# Sheet1.net
KiCad netlist of a schematic drawn in Altium Designer
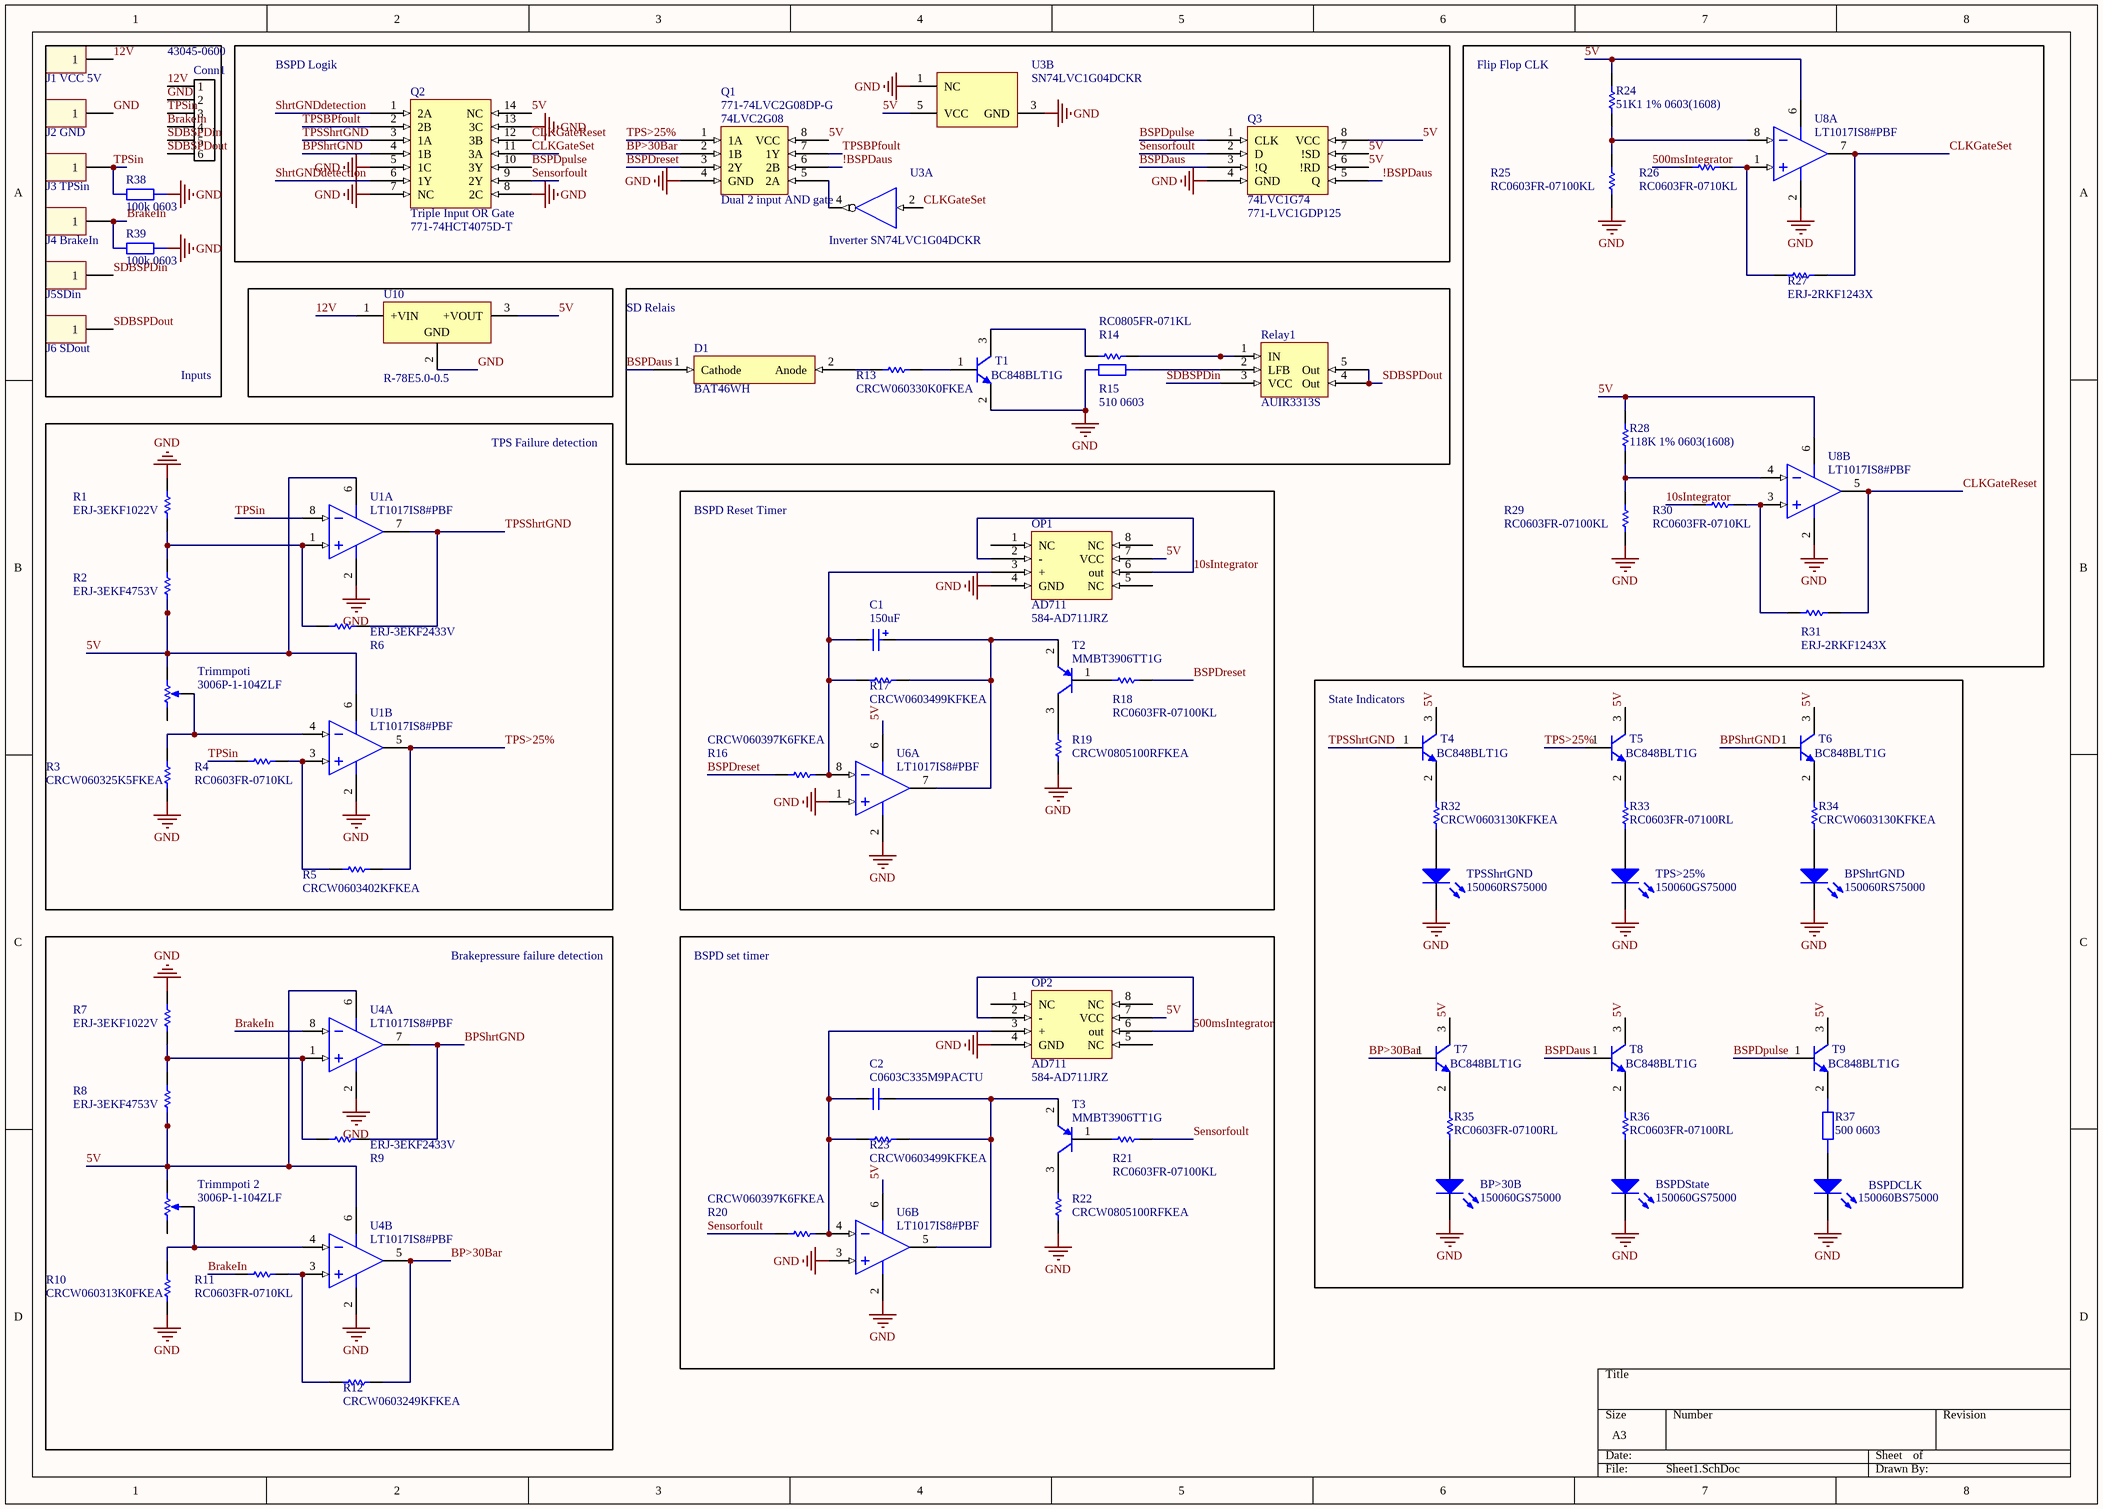
[diagram p0: Sheet1.SchDoc]

(export (version "E")
  (design (tool "Eeschema 10.0.6"))
  (components
    (comp (ref "BP>30B")
      (value "150060GS75000")
      (footprint "0603_A")
      (description "SMD mono-color Chip LED, WL-SMCW, Green")
      (fields (field (name "MANUFACTURER") "Wuerth Elektronik"))
      (libsource (lib "Altium Content Vault") (part "WE-LED_K1A2-2"))
    )
    (comp (ref "BPShrtGND")
      (value "150060RS75000")
      (footprint "0603_A")
      (description "SMD mono-color Chip LED, WL-SMCW, Red")
      (fields (field (name "MANUFACTURER") "Wuerth Elektronik"))
      (libsource (lib "Altium Content Vault") (part "WE-LED_K1A2-2"))
    )
    (comp (ref "BSPDCLK")
      (value "150060BS75000")
      (footprint "0603_A")
      (description "SMD mono-color Chip LED, WL-SMCW, Blue")
      (fields (field (name "MANUFACTURER") "Wuerth Elektronik"))
      (libsource (lib "Altium Content Vault") (part "WE-LED_K1A2-2"))
    )
    (comp (ref "BSPDState")
      (value "150060GS75000")
      (footprint "0603_A")
      (description "SMD mono-color Chip LED, WL-SMCW, Green")
      (fields (field (name "MANUFACTURER") "Wuerth Elektronik"))
      (libsource (lib "Altium Content Vault") (part "WE-LED_K1A2-2"))
    )
    (comp (ref "C1")
      (value "150uF")
      (footprint "WCAP-PSLC_10x12.4")
      (description "WCAP-PSLC Aluminum Polymer Capacitors, size Ф10x12.4mm, 25V DC, 150uF")
      (fields (field (name "PART NUMBER") "875075561006") (field (name "PUBLISHER") "Wurth Elektronik"))
      (libsource (lib "ALTIUM-WCAP-PSLC-rev17b") (part "875075561006"))
    )
    (comp (ref "C2")
      (value "C0603C335M9PACTU")
      (footprint "CAPC1608X90X35NL15T15")
      (fields (field (name "MANUFACTURER") "Kemet"))
      (libsource (lib "Altium Content Vault") (part "CAP"))
    )
    (comp (ref "Conn1")
      (value "43045-0600")
      (footprint "43045-0600")
      (description "Molex Micro-Fit 3.0 6-Pin\r\n600V\r\n8.5A")
      (libsource (lib "Standardbauteile") (part "MicroFit3.0 6-Pin"))
    )
    (comp (ref "D1")
      (value "BAT46WH")
      (footprint "DIOM2715X18N")
      (libsource (lib "Integrated_LibraryLukas") (part "BAT46WH"))
    )
    (comp (ref "J1 VCC 5V")
      (value "61300111121")
      (footprint "61300111121")
      (description "WR-PHD 2.54 mm THT Pin Header, 1p")
      (fields (field (name "PUBLISHER") "Wurth Elektronik"))
      (libsource (lib "ALTIUM-PHD_2_54_THT_DUAL_PIN_HEADER_6130XX21121") (part "61300111121"))
    )
    (comp (ref "J2 GND")
      (value "61300111121")
      (footprint "61300111121")
      (description "WR-PHD 2.54 mm THT Pin Header, 1p")
      (fields (field (name "PUBLISHER") "Wurth Elektronik"))
      (libsource (lib "ALTIUM-PHD_2_54_THT_DUAL_PIN_HEADER_6130XX21121") (part "61300111121"))
    )
    (comp (ref "J3 TPSin")
      (value "61300111121")
      (footprint "61300111121")
      (description "WR-PHD 2.54 mm THT Pin Header, 1p")
      (fields (field (name "PUBLISHER") "Wurth Elektronik"))
      (libsource (lib "ALTIUM-PHD_2_54_THT_DUAL_PIN_HEADER_6130XX21121") (part "61300111121"))
    )
    (comp (ref "J4 BrakeIn")
      (value "61300111121")
      (footprint "61300111121")
      (description "WR-PHD 2.54 mm THT Pin Header, 1p")
      (fields (field (name "PUBLISHER") "Wurth Elektronik"))
      (libsource (lib "ALTIUM-PHD_2_54_THT_DUAL_PIN_HEADER_6130XX21121") (part "61300111121"))
    )
    (comp (ref "J5SDin")
      (value "61300111121")
      (footprint "61300111121")
      (description "WR-PHD 2.54 mm THT Pin Header, 1p")
      (fields (field (name "PUBLISHER") "Wurth Elektronik"))
      (libsource (lib "ALTIUM-PHD_2_54_THT_DUAL_PIN_HEADER_6130XX21121") (part "61300111121"))
    )
    (comp (ref "J6 SDout")
      (value "61300111121")
      (footprint "61300111121")
      (description "WR-PHD 2.54 mm THT Pin Header, 1p")
      (fields (field (name "PUBLISHER") "Wurth Elektronik"))
      (libsource (lib "ALTIUM-PHD_2_54_THT_DUAL_PIN_HEADER_6130XX21121") (part "61300111121"))
    )
    (comp (ref "OP1")
      (value "AD711")
      (footprint "SOIC8; SOIC127P600X175-8N")
      (fields (field (name "SUPPLIER PART NUMBER 1") "584-AD711JRZ"))
      (libsource (lib "Integrated_LibraryLukas") (part "AD711"))
    )
    (comp (ref "OP2")
      (value "AD711")
      (footprint "SOIC8; SOIC127P600X175-8N")
      (fields (field (name "SUPPLIER PART NUMBER 1") "584-AD711JRZ"))
      (libsource (lib "Integrated_LibraryLukas") (part "AD711"))
    )
    (comp (ref "Q1")
      (value "Dual 2 input AND gate")
      (footprint "TSSOP8; TSOP65P400X110-8N")
      (fields (field (name "SUPPLIER PART NUMBER 1") "771-74LVC2G08DP-G"))
      (libsource (lib "Integrated_LibraryLukas") (part "74LVC2G08-Q100"))
    )
    (comp (ref "Q2")
      (value "Triple Input OR Gate")
      (footprint "SOIC14; SOIC127P600X175-14N")
      (fields (field (name "SUPPLIER PART NUMBER 1") "771-74HCT4075D-T"))
      (libsource (lib "Integrated_LibraryLukas") (part "74HCT4075D,653"))
    )
    (comp (ref "Q3")
      (value "74LVC1G74")
      (footprint "TSSOP8; TSOP65P400X110-8N")
      (fields (field (name "SUPPLIER PART NUMBER 1") "771-LVC1GDP125"))
      (libsource (lib "Integrated_LibraryLukas") (part "74LVC1G74"))
    )
    (comp (ref "R1")
      (value "ERJ-3EKF1022V")
      (footprint "RESC1608X55X30LL15T15")
      (fields (field (name "MANUFACTURER") "Panasonic"))
      (libsource (lib "Altium Content Vault") (part "RES"))
    )
    (comp (ref "R2")
      (value "ERJ-3EKF4753V")
      (footprint "RESC1608X55X30LL15T15")
      (fields (field (name "MANUFACTURER") "Panasonic"))
      (libsource (lib "Altium Content Vault") (part "RES"))
    )
    (comp (ref "R3")
      (value "CRCW060325K5FKEA")
      (footprint "RESC1609X50X30ML10T20")
      (fields (field (name "MANUFACTURER") "Vishay Dale"))
      (libsource (lib "Altium Content Vault") (part "RES"))
    )
    (comp (ref "R4")
      (value "RC0603FR-0710KL")
      (footprint "RESC1608X55X25ML10T15")
      (description "Chip Resistor, 10 KOhm, +/- 1%, 01 W, -55 to 155 degC, 0603 (1608 Metric), RoHS, Tape and Reel")
      (fields (field (name "MANUFACTURER") "Yageo") (field (name "TOLERANCE") "1%"))
      (libsource (lib "Altium Content Vault") (part "RES-2"))
    )
    (comp (ref "R5")
      (value "CRCW0603402KFKEA")
      (footprint "RESC1609X50X30ML10T20")
      (fields (field (name "MANUFACTURER") "Vishay Dale"))
      (libsource (lib "Altium Content Vault") (part "RES"))
    )
    (comp (ref "R6")
      (value "ERJ-3EKF2433V")
      (footprint "RESC1608X55X30ML15T15")
      (fields (field (name "MANUFACTURER") "Panasonic"))
      (libsource (lib "Altium Content Vault") (part "RES"))
    )
    (comp (ref "R7")
      (value "ERJ-3EKF1022V")
      (footprint "RESC1608X55X30LL15T15")
      (fields (field (name "MANUFACTURER") "Panasonic"))
      (libsource (lib "Altium Content Vault") (part "RES"))
    )
    (comp (ref "R8")
      (value "ERJ-3EKF4753V")
      (footprint "RESC1608X55X30LL15T15")
      (fields (field (name "MANUFACTURER") "Panasonic"))
      (libsource (lib "Altium Content Vault") (part "RES"))
    )
    (comp (ref "R9")
      (value "ERJ-3EKF2433V")
      (footprint "RESC1608X55X30ML15T15")
      (fields (field (name "MANUFACTURER") "Panasonic"))
      (libsource (lib "Altium Content Vault") (part "RES"))
    )
    (comp (ref "R10")
      (value "CRCW060313K0FKEA")
      (footprint "RESC1609X50X30NL10T20")
      (fields (field (name "MANUFACTURER") "Vishay Dale"))
      (libsource (lib "Altium Content Vault") (part "RES"))
    )
    (comp (ref "R11")
      (value "RC0603FR-0710KL")
      (footprint "RESC1608X55X25ML10T15")
      (description "Chip Resistor, 10 KOhm, +/- 1%, 01 W, -55 to 155 degC, 0603 (1608 Metric), RoHS, Tape and Reel")
      (fields (field (name "MANUFACTURER") "Yageo") (field (name "TOLERANCE") "1%"))
      (libsource (lib "Altium Content Vault") (part "RES-2"))
    )
    (comp (ref "R12")
      (value "CRCW0603249KFKEA")
      (footprint "RESC1609X50X30NL10T20")
      (fields (field (name "MANUFACTURER") "Vishay Dale"))
      (libsource (lib "Altium Content Vault") (part "RES"))
    )
    (comp (ref "R13")
      (value "CRCW060330K0FKEA")
      (footprint "RESC1609X50X30LL10T20")
      (fields (field (name "MANUFACTURER") "Vishay Dale"))
      (libsource (lib "Altium Content Vault") (part "RES"))
    )
    (comp (ref "R14")
      (value "RC0805FR-071KL")
      (footprint "RESC2013X60X35ML10T20")
      (description "Chip Resistor, 1 KOhm, +/- 1%, 125 mW, -55 to 155 degC, 0805 (2012 Metric), RoHS, Tape and Reel")
      (fields (field (name "TOLERANCE") "1%") (field (name "MANUFACTURER") "Yageo"))
      (libsource (lib "Altium Content Vault") (part "RES-2"))
    )
    (comp (ref "R15")
      (value "510 0603")
      (footprint "STACKPOLE CSR0603")
      (description "Resistor with multiple footprints")
      (fields (field (name "Comment") "SMD Resistor"))
      (libsource (lib "Standardbauteile") (part "SMD Resistor"))
    )
    (comp (ref "R16")
      (value "CRCW060397K6FKEA")
      (footprint "RESC1609X50X30LL10T20")
      (fields (field (name "MANUFACTURER") "Vishay Dale"))
      (libsource (lib "Altium Content Vault") (part "RES"))
    )
    (comp (ref "R17")
      (value "CRCW0603499KFKEA")
      (footprint "RESC1609X50X30NL10T20")
      (fields (field (name "MANUFACTURER") "Vishay Dale"))
      (libsource (lib "Altium Content Vault") (part "RES"))
    )
    (comp (ref "R18")
      (value "RC0603FR-07100KL")
      (footprint "RESC1608X55X25ML10T15")
      (description "Chip Resistor, 100 KOhm, +/- 1%, 0.1 W, -55 to 155 degC, 0603 (1608 Metric), RoHS, Tape and Reel")
      (fields (field (name "MANUFACTURER") "Yageo") (field (name "TOLERANCE") "1%"))
      (libsource (lib "Altium Content Vault") (part "RES-2"))
    )
    (comp (ref "R19")
      (value "CRCW0805100RFKEA")
      (footprint "RESC2013X50X30LL20T20")
      (fields (field (name "MANUFACTURER") "Vishay Dale"))
      (libsource (lib "Altium Content Vault") (part "RES"))
    )
    (comp (ref "R20")
      (value "CRCW060397K6FKEA")
      (footprint "RESC1609X50X30LL10T20")
      (fields (field (name "MANUFACTURER") "Vishay Dale"))
      (libsource (lib "Altium Content Vault") (part "RES"))
    )
    (comp (ref "R21")
      (value "RC0603FR-07100KL")
      (footprint "RESC1608X55X25ML10T15")
      (description "Chip Resistor, 100 KOhm, +/- 1%, 0.1 W, -55 to 155 degC, 0603 (1608 Metric), RoHS, Tape and Reel")
      (fields (field (name "MANUFACTURER") "Yageo") (field (name "TOLERANCE") "1%"))
      (libsource (lib "Altium Content Vault") (part "RES-2"))
    )
    (comp (ref "R22")
      (value "CRCW0805100RFKEA")
      (footprint "RESC2013X50X30LL20T20")
      (fields (field (name "MANUFACTURER") "Vishay Dale"))
      (libsource (lib "Altium Content Vault") (part "RES"))
    )
    (comp (ref "R23")
      (value "CRCW0603499KFKEA")
      (footprint "RESC1609X50X30NL10T20")
      (fields (field (name "MANUFACTURER") "Vishay Dale"))
      (libsource (lib "Altium Content Vault") (part "RES"))
    )
    (comp (ref "R24")
      (value "51K1 1% 0603(1608)")
      (footprint "RESC0603(1608)_L")
      (description "51K1 0.1W 1% 0603 (1608 Metric)  SMD")
      (fields (field (name "TOLERANCE") "1 %") (field (name "POWER") "0.1 W"))
      (libsource (lib "Altium Content Vault") (part "RES"))
    )
    (comp (ref "R25")
      (value "RC0603FR-07100KL")
      (footprint "RESC1608X55X25ML10T15")
      (description "Chip Resistor, 100 KOhm, +/- 1%, 0.1 W, -55 to 155 degC, 0603 (1608 Metric), RoHS, Tape and Reel")
      (fields (field (name "MANUFACTURER") "Yageo") (field (name "TOLERANCE") "1%"))
      (libsource (lib "Altium Content Vault") (part "RES-2"))
    )
    (comp (ref "R26")
      (value "RC0603FR-0710KL")
      (footprint "RESC1608X55X25ML10T15")
      (description "Chip Resistor, 10 KOhm, +/- 1%, 01 W, -55 to 155 degC, 0603 (1608 Metric), RoHS, Tape and Reel")
      (fields (field (name "MANUFACTURER") "Yageo") (field (name "TOLERANCE") "1%"))
      (libsource (lib "Altium Content Vault") (part "RES-2"))
    )
    (comp (ref "R27")
      (value "ERJ-2RKF1243X")
      (footprint "RESC1005X40X25NL05T05")
      (fields (field (name "MANUFACTURER") "Panasonic"))
      (libsource (lib "Altium Content Vault") (part "RES"))
    )
    (comp (ref "R28")
      (value "118K 1% 0603(1608)")
      (footprint "RESC0603(1608)_M")
      (description "118K 0.1W 1% 0603 (1608 Metric)  SMD")
      (fields (field (name "POWER") "0.1 W") (field (name "TOLERANCE") "1 %"))
      (libsource (lib "Altium Content Vault") (part "RES"))
    )
    (comp (ref "R29")
      (value "RC0603FR-07100KL")
      (footprint "RESC1608X55X25ML10T15")
      (description "Chip Resistor, 100 KOhm, +/- 1%, 0.1 W, -55 to 155 degC, 0603 (1608 Metric), RoHS, Tape and Reel")
      (fields (field (name "MANUFACTURER") "Yageo") (field (name "TOLERANCE") "1%"))
      (libsource (lib "Altium Content Vault") (part "RES-2"))
    )
    (comp (ref "R30")
      (value "RC0603FR-0710KL")
      (footprint "RESC1608X55X25ML10T15")
      (description "Chip Resistor, 10 KOhm, +/- 1%, 01 W, -55 to 155 degC, 0603 (1608 Metric), RoHS, Tape and Reel")
      (fields (field (name "MANUFACTURER") "Yageo") (field (name "TOLERANCE") "1%"))
      (libsource (lib "Altium Content Vault") (part "RES-2"))
    )
    (comp (ref "R31")
      (value "ERJ-2RKF1243X")
      (footprint "RESC1005X40X25NL05T05")
      (fields (field (name "MANUFACTURER") "Panasonic"))
      (libsource (lib "Altium Content Vault") (part "RES"))
    )
    (comp (ref "R32")
      (value "CRCW0603130KFKEA")
      (footprint "RESC1609X50X30NL10T20")
      (fields (field (name "MANUFACTURER") "Vishay Dale"))
      (libsource (lib "Altium Content Vault") (part "RES"))
    )
    (comp (ref "R33")
      (value "RC0603FR-07100RL")
      (footprint "RESC1608X55X25ML10T15")
      (description "Chip Resistor, 100 Ohm, +/- 1%, 0.1 W, -55 to 155 degC, 0603 (1608 Metric), RoHS, Tape and Reel")
      (fields (field (name "TOLERANCE") "1%") (field (name "MANUFACTURER") "Yageo"))
      (libsource (lib "Altium Content Vault") (part "RES-2"))
    )
    (comp (ref "R34")
      (value "CRCW0603130KFKEA")
      (footprint "RESC1609X50X30NL10T20")
      (fields (field (name "MANUFACTURER") "Vishay Dale"))
      (libsource (lib "Altium Content Vault") (part "RES"))
    )
    (comp (ref "R35")
      (value "RC0603FR-07100RL")
      (footprint "RESC1608X55X25ML10T15")
      (description "Chip Resistor, 100 Ohm, +/- 1%, 0.1 W, -55 to 155 degC, 0603 (1608 Metric), RoHS, Tape and Reel")
      (fields (field (name "TOLERANCE") "1%") (field (name "MANUFACTURER") "Yageo"))
      (libsource (lib "Altium Content Vault") (part "RES-2"))
    )
    (comp (ref "R36")
      (value "RC0603FR-07100RL")
      (footprint "RESC1608X55X25ML10T15")
      (description "Chip Resistor, 100 Ohm, +/- 1%, 0.1 W, -55 to 155 degC, 0603 (1608 Metric), RoHS, Tape and Reel")
      (fields (field (name "TOLERANCE") "1%") (field (name "MANUFACTURER") "Yageo"))
      (libsource (lib "Altium Content Vault") (part "RES-2"))
    )
    (comp (ref "R37")
      (value "500 0603")
      (footprint "STACKPOLE CSR0603")
      (description "Resistor with multiple footprints")
      (fields (field (name "Comment") "SMD Resistor"))
      (libsource (lib "Standardbauteile") (part "SMD Resistor"))
    )
    (comp (ref "R38")
      (value "100k 0603")
      (footprint "STACKPOLE CSR0603")
      (description "Resistor with multiple footprints")
      (fields (field (name "Comment") "SMD Resistor"))
      (libsource (lib "Standardbauteile") (part "SMD Resistor"))
    )
    (comp (ref "R39")
      (value "100k 0603")
      (footprint "STACKPOLE CSR0603")
      (description "Resistor with multiple footprints")
      (fields (field (name "Comment") "SMD Resistor"))
      (libsource (lib "Standardbauteile") (part "SMD Resistor"))
    )
    (comp (ref "Relay1")
      (value "AUIR3313S")
      (footprint "D2PAK5 ;DPAK228P1524X483-5N")
      (libsource (lib "Integrated_LibraryLukas") (part "AUIR3313S"))
    )
    (comp (ref "T1")
      (value "BC848BLT1G")
      (footprint "ONSC-SOT-23-3-318-08_V")
      (description "General Purpose Transistor, NPN Silicon, 3-Pin SOT-23, Pb-Free, Tape and Reel")
      (fields (field (name "MANUFACTURER") "On Semiconductor"))
      (libsource (lib "Altium Content Vault") (part "ONSC-NPN-B1E2C3-3"))
    )
    (comp (ref "T2")
      (value "MMBT3906TT1G")
      (footprint "ONSC-SC-75-3-463-01_V")
      (description "General Purpose Transistor, PNP Silicon, 3-Pin SC-75, Pb-Free, Tape and Reel")
      (fields (field (name "MANUFACTURER") "On Semiconductor"))
      (libsource (lib "Altium Content Vault") (part "ONSC-PNP-B1E2C3-3"))
    )
    (comp (ref "T3")
      (value "MMBT3906TT1G")
      (footprint "ONSC-SC-75-3-463-01_V")
      (description "General Purpose Transistor, PNP Silicon, 3-Pin SC-75, Pb-Free, Tape and Reel")
      (fields (field (name "MANUFACTURER") "On Semiconductor"))
      (libsource (lib "Altium Content Vault") (part "ONSC-PNP-B1E2C3-3"))
    )
    (comp (ref "T4")
      (value "BC848BLT1G")
      (footprint "ONSC-SOT-23-3-318-08_V")
      (description "General Purpose Transistor, NPN Silicon, 3-Pin SOT-23, Pb-Free, Tape and Reel")
      (fields (field (name "MANUFACTURER") "On Semiconductor"))
      (libsource (lib "Altium Content Vault") (part "ONSC-NPN-B1E2C3-3"))
    )
    (comp (ref "T5")
      (value "BC848BLT1G")
      (footprint "ONSC-SOT-23-3-318-08_V")
      (description "General Purpose Transistor, NPN Silicon, 3-Pin SOT-23, Pb-Free, Tape and Reel")
      (fields (field (name "MANUFACTURER") "On Semiconductor"))
      (libsource (lib "Altium Content Vault") (part "ONSC-NPN-B1E2C3-3"))
    )
    (comp (ref "T6")
      (value "BC848BLT1G")
      (footprint "ONSC-SOT-23-3-318-08_V")
      (description "General Purpose Transistor, NPN Silicon, 3-Pin SOT-23, Pb-Free, Tape and Reel")
      (fields (field (name "MANUFACTURER") "On Semiconductor"))
      (libsource (lib "Altium Content Vault") (part "ONSC-NPN-B1E2C3-3"))
    )
    (comp (ref "T7")
      (value "BC848BLT1G")
      (footprint "ONSC-SOT-23-3-318-08_V")
      (description "General Purpose Transistor, NPN Silicon, 3-Pin SOT-23, Pb-Free, Tape and Reel")
      (fields (field (name "MANUFACTURER") "On Semiconductor"))
      (libsource (lib "Altium Content Vault") (part "ONSC-NPN-B1E2C3-3"))
    )
    (comp (ref "T8")
      (value "BC848BLT1G")
      (footprint "ONSC-SOT-23-3-318-08_V")
      (description "General Purpose Transistor, NPN Silicon, 3-Pin SOT-23, Pb-Free, Tape and Reel")
      (fields (field (name "MANUFACTURER") "On Semiconductor"))
      (libsource (lib "Altium Content Vault") (part "ONSC-NPN-B1E2C3-3"))
    )
    (comp (ref "T9")
      (value "BC848BLT1G")
      (footprint "ONSC-SOT-23-3-318-08_V")
      (description "General Purpose Transistor, NPN Silicon, 3-Pin SOT-23, Pb-Free, Tape and Reel")
      (fields (field (name "MANUFACTURER") "On Semiconductor"))
      (libsource (lib "Altium Content Vault") (part "ONSC-NPN-B1E2C3-3"))
    )
    (comp (ref "TPS>25%")
      (value "150060GS75000")
      (footprint "0603_A")
      (description "SMD mono-color Chip LED, WL-SMCW, Green")
      (fields (field (name "MANUFACTURER") "Wuerth Elektronik"))
      (libsource (lib "Altium Content Vault") (part "WE-LED_K1A2-2"))
    )
    (comp (ref "TPSShrtGND")
      (value "150060RS75000")
      (footprint "0603_A")
      (description "SMD mono-color Chip LED, WL-SMCW, Red")
      (fields (field (name "MANUFACTURER") "Wuerth Elektronik"))
      (libsource (lib "Altium Content Vault") (part "WE-LED_K1A2-2"))
    )
    (comp (ref "Trimmpoti")
      (value "3006P-1-104ZLF")
      (footprint "BOUR-3006P-3_V")
      (description "Trimming Potentiometer, 100K Ohm +/- 10%, -55 to 125 degC, 3-Pin 19.05 x 4.83 x 6.6 mm THD, RoHS")
      (fields (field (name "MANUFACTURER") "Bourns"))
      (libsource (lib "Altium Content Vault") (part "BOUR-3006P-3"))
    )
    (comp (ref "Trimmpoti 2")
      (value "3006P-1-104ZLF")
      (footprint "BOUR-3006P-3_V")
      (description "Trimming Potentiometer, 100K Ohm +/- 10%, -55 to 125 degC, 3-Pin 19.05 x 4.83 x 6.6 mm THD, RoHS")
      (fields (field (name "MANUFACTURER") "Bourns"))
      (libsource (lib "Altium Content Vault") (part "BOUR-3006P-3"))
    )
    (comp (ref "U1")
      (value "LT1017IS8#PBF")
      (footprint "LT-S8_N")
      (description "Micropower Comparator, 2 Channels, 1.2 to 40 V, -40 to +85 degC, 8-pin SOP (S8)")
      (fields (field (name "MANUFACTURER") "Linear Technology") (field (name "GENERIC PART NUMBER") "LT1017"))
      (libsource (lib "Altium Content Vault") (part "LT-LT1017-SO8"))
    )
    (comp (ref "U3")
      (value "Inverter SN74LVC1G04DCKR")
      (footprint "DCK0005A_N")
      (description "Single Inverter, DCK0005A, LARGE T&R")
      (fields
        (field (name "GENERIC PART NUMBER") "SN74LVC1G04")
        (field (name "MANUFACTURER") "Texas Instruments")
      )
      (libsource (lib "Altium Content Vault") (part "TI-SN74XXX1XX4-XX-5"))
    )
    (comp (ref "U4")
      (value "LT1017IS8#PBF")
      (footprint "LT-S8_N")
      (description "Micropower Comparator, 2 Channels, 1.2 to 40 V, -40 to +85 degC, 8-pin SOP (S8)")
      (fields (field (name "MANUFACTURER") "Linear Technology") (field (name "GENERIC PART NUMBER") "LT1017"))
      (libsource (lib "Altium Content Vault") (part "LT-LT1017-SO8"))
    )
    (comp (ref "U6")
      (value "LT1017IS8#PBF")
      (footprint "LT-S8_N")
      (description "Micropower Comparator, 2 Channels, 1.2 to 40 V, -40 to +85 degC, 8-pin SOP (S8)")
      (fields (field (name "MANUFACTURER") "Linear Technology") (field (name "GENERIC PART NUMBER") "LT1017"))
      (libsource (lib "Altium Content Vault") (part "LT-LT1017-SO8"))
    )
    (comp (ref "U8")
      (value "LT1017IS8#PBF")
      (footprint "LT-S8_N")
      (description "Micropower Comparator, 2 Channels, 1.2 to 40 V, -40 to +85 degC, 8-pin SOP (S8)")
      (fields (field (name "MANUFACTURER") "Linear Technology") (field (name "GENERIC PART NUMBER") "LT1017"))
      (libsource (lib "Altium Content Vault") (part "LT-LT1017-SO8"))
    )
    (comp (ref "U10")
      (value "R-78E5.0-0.5")
      (footprint "REPO-R-78E-0.5-3_V")
      (description "DC/DC-Converter, 5 V Single Output, 500 mA, -40 to 85 degC, 3-Pin THD, RoHS, Tube")
      (fields (field (name "MANUFACTURER") "Recom Power"))
      (libsource (lib "Altium Content Vault") (part "REPO-R-78XX-3"))
    )
  )
  (nets
    (net (code "1") (name "/!BSPDaus") (class "Default")
      (node (ref "Q1") (pin "6") (pinfunction "2B_6") (pintype "input"))
      (node (ref "Q3") (pin "5") (pinfunction "Q_5") (pintype "input"))
    )
    (net (code "2") (name "/5V") (class "Default")
      (node (ref "OP1") (pin "7") (pinfunction "VCC_7") (pintype "input"))
      (node (ref "OP2") (pin "7") (pinfunction "VCC_7") (pintype "input"))
      (node (ref "Q1") (pin "8") (pinfunction "VCC_8") (pintype "input"))
      (node (ref "Q2") (pin "14") (pinfunction "NC_14") (pintype "input"))
      (node (ref "Q3") (pin "6") (pinfunction "!RD_6") (pintype "input"))
      (node (ref "Q3") (pin "7") (pinfunction "!SD_7") (pintype "input"))
      (node (ref "Q3") (pin "8") (pinfunction "VCC_8") (pintype "input"))
      (node (ref "R2") (pin "1") (pinfunction "1_1") (pintype "passive"))
      (node (ref "R24") (pin "2") (pinfunction "2_2") (pintype "passive"))
      (node (ref "R28") (pin "2") (pinfunction "2_2") (pintype "passive"))
      (node (ref "R8") (pin "1") (pinfunction "1_1") (pintype "passive"))
      (node (ref "T4") (pin "3") (pinfunction "C_3") (pintype "passive"))
      (node (ref "T5") (pin "3") (pinfunction "C_3") (pintype "passive"))
      (node (ref "T6") (pin "3") (pinfunction "C_3") (pintype "passive"))
      (node (ref "T7") (pin "3") (pinfunction "C_3") (pintype "passive"))
      (node (ref "T8") (pin "3") (pinfunction "C_3") (pintype "passive"))
      (node (ref "T9") (pin "3") (pinfunction "C_3") (pintype "passive"))
      (node (ref "Trimmpoti") (pin "1") (pinfunction "CCW_1") (pintype "passive"))
      (node (ref "Trimmpoti 2") (pin "1") (pinfunction "CCW_1") (pintype "passive"))
      (node (ref "U1") (pin "6") (pinfunction "V+_6") (pintype "power_in"))
      (node (ref "U10") (pin "3") (pinfunction "+VOUT_3") (pintype "power_in"))
      (node (ref "U3") (pin "5") (pinfunction "VCC_5") (pintype "power_in"))
      (node (ref "U4") (pin "6") (pinfunction "V+_6") (pintype "power_in"))
      (node (ref "U6") (pin "6") (pinfunction "V+_6") (pintype "power_in"))
      (node (ref "U8") (pin "6") (pinfunction "V+_6") (pintype "power_in"))
    )
    (net (code "3") (name "/10sIntegrator") (class "Default")
      (node (ref "OP1") (pin "2") (pinfunction "-_2") (pintype "input"))
      (node (ref "OP1") (pin "6") (pinfunction "out_6") (pintype "input"))
      (node (ref "R30") (pin "1") (pinfunction "1_1") (pintype "passive"))
    )
    (net (code "4") (name "/12V") (class "Default")
      (node (ref "Conn1") (pin "1") (pinfunction "1_1") (pintype "passive"))
      (node (ref "J1 VCC 5V") (pin "1") (pinfunction "1_1") (pintype "passive"))
      (node (ref "U10") (pin "1") (pinfunction "+VIN_1") (pintype "power_in"))
    )
    (net (code "5") (name "/500msIntegrator") (class "Default")
      (node (ref "OP2") (pin "2") (pinfunction "-_2") (pintype "input"))
      (node (ref "OP2") (pin "6") (pinfunction "out_6") (pintype "input"))
      (node (ref "R26") (pin "1") (pinfunction "1_1") (pintype "passive"))
    )
    (net (code "6") (name "/BP>30Bar") (class "Default")
      (node (ref "Q1") (pin "2") (pinfunction "1B_2") (pintype "input"))
      (node (ref "R12") (pin "2") (pinfunction "2_2") (pintype "passive"))
      (node (ref "T7") (pin "1") (pinfunction "B_1") (pintype "passive"))
      (node (ref "U4") (pin "5") (pinfunction "OUT_B_5") (pintype "open_collector"))
    )
    (net (code "7") (name "/BPShrtGND") (class "Default")
      (node (ref "Q2") (pin "4") (pinfunction "1B_4") (pintype "input"))
      (node (ref "R9") (pin "2") (pinfunction "2_2") (pintype "passive"))
      (node (ref "T6") (pin "1") (pinfunction "B_1") (pintype "passive"))
      (node (ref "U4") (pin "7") (pinfunction "OUT_A_7") (pintype "open_collector"))
    )
    (net (code "8") (name "/BSPDaus") (class "Default")
      (node (ref "D1") (pin "1") (pinfunction "Cathode_1") (pintype "input"))
      (node (ref "Q3") (pin "3") (pinfunction "!Q_3") (pintype "input"))
      (node (ref "T8") (pin "1") (pinfunction "B_1") (pintype "passive"))
    )
    (net (code "9") (name "/BSPDpulse") (class "Default")
      (node (ref "Q2") (pin "10") (pinfunction "3Y_10") (pintype "input"))
      (node (ref "Q3") (pin "1") (pinfunction "CLK_1") (pintype "input"))
      (node (ref "T9") (pin "1") (pinfunction "B_1") (pintype "passive"))
    )
    (net (code "10") (name "/BSPDreset") (class "Default")
      (node (ref "Q1") (pin "3") (pinfunction "2Y_3") (pintype "input"))
      (node (ref "R16") (pin "1") (pinfunction "1_1") (pintype "passive"))
      (node (ref "R18") (pin "1") (pinfunction "1_1") (pintype "passive"))
    )
    (net (code "11") (name "/BrakeIn") (class "Default")
      (node (ref "Conn1") (pin "4") (pinfunction "4_4") (pintype "passive"))
      (node (ref "J4 BrakeIn") (pin "1") (pinfunction "1_1") (pintype "passive"))
      (node (ref "R11") (pin "1") (pinfunction "1_1") (pintype "passive"))
      (node (ref "R39") (pin "1") (pinfunction "1_1") (pintype "passive"))
      (node (ref "U4") (pin "8") (pinfunction "-IN_A_8") (pintype "input"))
    )
    (net (code "12") (name "/CLKGateReset") (class "Default")
      (node (ref "Q2") (pin "12") (pinfunction "3B_12") (pintype "input"))
      (node (ref "R31") (pin "2") (pinfunction "2_2") (pintype "passive"))
      (node (ref "U8") (pin "5") (pinfunction "OUT_B_5") (pintype "open_collector"))
    )
    (net (code "13") (name "/CLKGateSet") (class "Default")
      (node (ref "Q2") (pin "11") (pinfunction "3A_11") (pintype "input"))
      (node (ref "R27") (pin "2") (pinfunction "2_2") (pintype "passive"))
      (node (ref "U3") (pin "2") (pinfunction "A_2") (pintype "input"))
      (node (ref "U8") (pin "7") (pinfunction "OUT_A_7") (pintype "open_collector"))
    )
    (net (code "14") (name "/SDBSPDin") (class "Default")
      (node (ref "Conn1") (pin "5") (pinfunction "5_5") (pintype "passive"))
      (node (ref "J5SDin") (pin "1") (pinfunction "1_1") (pintype "passive"))
      (node (ref "Relay1") (pin "3") (pinfunction "VCC_3") (pintype "input"))
    )
    (net (code "15") (name "/SDBSPDout") (class "Default")
      (node (ref "Conn1") (pin "6") (pinfunction "6_6") (pintype "passive"))
      (node (ref "J6 SDout") (pin "1") (pinfunction "1_1") (pintype "passive"))
      (node (ref "Relay1") (pin "4") (pinfunction "Out_4") (pintype "input"))
      (node (ref "Relay1") (pin "5") (pinfunction "Out_5") (pintype "input"))
    )
    (net (code "16") (name "/Sensorfoult") (class "Default")
      (node (ref "Q2") (pin "9") (pinfunction "2Y_9") (pintype "input"))
      (node (ref "Q3") (pin "2") (pinfunction "D_2") (pintype "input"))
      (node (ref "R20") (pin "1") (pinfunction "1_1") (pintype "passive"))
      (node (ref "R21") (pin "1") (pinfunction "1_1") (pintype "passive"))
    )
    (net (code "17") (name "/ShrtGNDdetection") (class "Default")
      (node (ref "Q2") (pin "1") (pinfunction "2A_1") (pintype "input"))
      (node (ref "Q2") (pin "6") (pinfunction "1Y_6") (pintype "input"))
    )
    (net (code "18") (name "/TPS>25%") (class "Default")
      (node (ref "Q1") (pin "1") (pinfunction "1A_1") (pintype "input"))
      (node (ref "R5") (pin "2") (pinfunction "2_2") (pintype "passive"))
      (node (ref "T5") (pin "1") (pinfunction "B_1") (pintype "passive"))
      (node (ref "U1") (pin "5") (pinfunction "OUT_B_5") (pintype "open_collector"))
    )
    (net (code "19") (name "/TPSBPfoult") (class "Default")
      (node (ref "Q1") (pin "7") (pinfunction "1Y_7") (pintype "input"))
      (node (ref "Q2") (pin "2") (pinfunction "2B_2") (pintype "input"))
    )
    (net (code "20") (name "/TPSShrtGND") (class "Default")
      (node (ref "Q2") (pin "3") (pinfunction "1A_3") (pintype "input"))
      (node (ref "R6") (pin "2") (pinfunction "2_2") (pintype "passive"))
      (node (ref "T4") (pin "1") (pinfunction "B_1") (pintype "passive"))
      (node (ref "U1") (pin "7") (pinfunction "OUT_A_7") (pintype "open_collector"))
    )
    (net (code "21") (name "/TPSin") (class "Default")
      (node (ref "Conn1") (pin "3") (pinfunction "3_3") (pintype "passive"))
      (node (ref "J3 TPSin") (pin "1") (pinfunction "1_1") (pintype "passive"))
      (node (ref "R38") (pin "1") (pinfunction "1_1") (pintype "passive"))
      (node (ref "R4") (pin "1") (pinfunction "1_1") (pintype "passive"))
      (node (ref "U1") (pin "8") (pinfunction "-IN_A_8") (pintype "input"))
    )
    (net (code "22") (name "GND") (class "Default")
      (node (ref "BP>30B") (pin "1") (pinfunction "K_1") (pintype "passive"))
      (node (ref "BPShrtGND") (pin "1") (pinfunction "K_1") (pintype "passive"))
      (node (ref "BSPDCLK") (pin "1") (pinfunction "K_1") (pintype "passive"))
      (node (ref "BSPDState") (pin "1") (pinfunction "K_1") (pintype "passive"))
      (node (ref "Conn1") (pin "2") (pinfunction "2_2") (pintype "passive"))
      (node (ref "J2 GND") (pin "1") (pinfunction "1_1") (pintype "passive"))
      (node (ref "OP1") (pin "4") (pinfunction "GND_4") (pintype "input"))
      (node (ref "OP2") (pin "4") (pinfunction "GND_4") (pintype "input"))
      (node (ref "Q1") (pin "4") (pinfunction "GND_4") (pintype "input"))
      (node (ref "Q2") (pin "13") (pinfunction "3C_13") (pintype "input"))
      (node (ref "Q2") (pin "5") (pinfunction "1C_5") (pintype "input"))
      (node (ref "Q2") (pin "7") (pinfunction "NC_7") (pintype "input"))
      (node (ref "Q2") (pin "8") (pinfunction "2C_8") (pintype "input"))
      (node (ref "Q3") (pin "4") (pinfunction "GND_4") (pintype "input"))
      (node (ref "R1") (pin "2") (pinfunction "2_2") (pintype "passive"))
      (node (ref "R10") (pin "1") (pinfunction "1_1") (pintype "passive"))
      (node (ref "R15") (pin "1") (pinfunction "1_1") (pintype "passive"))
      (node (ref "R19") (pin "2") (pinfunction "2_2") (pintype "passive"))
      (node (ref "R22") (pin "2") (pinfunction "2_2") (pintype "passive"))
      (node (ref "R25") (pin "1") (pinfunction "1_1") (pintype "passive"))
      (node (ref "R29") (pin "1") (pinfunction "1_1") (pintype "passive"))
      (node (ref "R3") (pin "1") (pinfunction "1_1") (pintype "passive"))
      (node (ref "R38") (pin "2") (pinfunction "2_2") (pintype "passive"))
      (node (ref "R39") (pin "2") (pinfunction "2_2") (pintype "passive"))
      (node (ref "R7") (pin "2") (pinfunction "2_2") (pintype "passive"))
      (node (ref "T1") (pin "2") (pinfunction "E_2") (pintype "passive"))
      (node (ref "TPS>25%") (pin "1") (pinfunction "K_1") (pintype "passive"))
      (node (ref "TPSShrtGND") (pin "1") (pinfunction "K_1") (pintype "passive"))
      (node (ref "U1") (pin "2") (pinfunction "V-_2") (pintype "power_in"))
      (node (ref "U10") (pin "2") (pinfunction "GND_2") (pintype "power_in"))
      (node (ref "U3") (pin "1") (pinfunction "NC_1") (pintype "passive"))
      (node (ref "U3") (pin "3") (pinfunction "GND_3") (pintype "power_in"))
      (node (ref "U4") (pin "2") (pinfunction "V-_2") (pintype "power_in"))
      (node (ref "U6") (pin "1") (pinfunction "+IN_A_1") (pintype "input"))
      (node (ref "U6") (pin "2") (pinfunction "V-_2") (pintype "power_in"))
      (node (ref "U6") (pin "3") (pinfunction "+IN_B_3") (pintype "input"))
      (node (ref "U8") (pin "2") (pinfunction "V-_2") (pintype "power_in"))
    )
    (net (code "23") (name "Net-(BP>30B-A)") (class "Default")
      (node (ref "BP>30B") (pin "2") (pinfunction "A_2") (pintype "passive"))
      (node (ref "R35") (pin "2") (pinfunction "2_2") (pintype "passive"))
    )
    (net (code "24") (name "Net-(BPShrtGND-A)") (class "Default")
      (node (ref "BPShrtGND") (pin "2") (pinfunction "A_2") (pintype "passive"))
      (node (ref "R34") (pin "1") (pinfunction "1_1") (pintype "passive"))
    )
    (net (code "25") (name "Net-(BSPDCLK-A)") (class "Default")
      (node (ref "BSPDCLK") (pin "2") (pinfunction "A_2") (pintype "passive"))
      (node (ref "R37") (pin "1") (pinfunction "1_1") (pintype "passive"))
    )
    (net (code "26") (name "Net-(BSPDState-A)") (class "Default")
      (node (ref "BSPDState") (pin "2") (pinfunction "A_2") (pintype "passive"))
      (node (ref "R36") (pin "2") (pinfunction "2_2") (pintype "passive"))
    )
    (net (code "27") (name "Net-(C1-N)") (class "Default")
      (node (ref "C1") (pin "2") (pinfunction "N_2") (pintype "passive"))
      (node (ref "OP1") (pin "3") (pinfunction "+_3") (pintype "input"))
      (node (ref "R16") (pin "2") (pinfunction "2_2") (pintype "passive"))
      (node (ref "R17") (pin "1") (pinfunction "1_1") (pintype "passive"))
      (node (ref "U6") (pin "8") (pinfunction "-IN_A_8") (pintype "input"))
    )
    (net (code "28") (name "Net-(C1-P)") (class "Default")
      (node (ref "C1") (pin "1") (pinfunction "P_1") (pintype "passive"))
      (node (ref "R17") (pin "2") (pinfunction "2_2") (pintype "passive"))
      (node (ref "T2") (pin "2") (pinfunction "E_2") (pintype "passive"))
      (node (ref "U6") (pin "7") (pinfunction "OUT_A_7") (pintype "open_collector"))
    )
    (net (code "29") (name "Net-(D1-Anode)") (class "Default")
      (node (ref "D1") (pin "2") (pinfunction "Anode_2") (pintype "input"))
      (node (ref "R13") (pin "1") (pinfunction "1_1") (pintype "passive"))
    )
    (net (code "30") (name "Net-(OP2-+)") (class "Default")
      (node (ref "C2") (pin "1") (pinfunction "1_1") (pintype "passive"))
      (node (ref "OP2") (pin "3") (pinfunction "+_3") (pintype "input"))
      (node (ref "R20") (pin "2") (pinfunction "2_2") (pintype "passive"))
      (node (ref "R23") (pin "1") (pinfunction "1_1") (pintype "passive"))
      (node (ref "U6") (pin "4") (pinfunction "-IN_B_4") (pintype "input"))
    )
    (net (code "31") (name "Net-(Q1-2A)") (class "Default")
      (node (ref "Q1") (pin "5") (pinfunction "2A_5") (pintype "input"))
      (node (ref "U3") (pin "4") (pinfunction "Y_4") (pintype "output"))
    )
    (net (code "32") (name "Net-(Relay1-IN)") (class "Default")
      (node (ref "R14") (pin "2") (pinfunction "2_2") (pintype "passive"))
      (node (ref "Relay1") (pin "1") (pinfunction "IN_1") (pintype "input"))
    )
    (net (code "33") (name "Net-(Relay1-LFB)") (class "Default")
      (node (ref "R15") (pin "2") (pinfunction "2_2") (pintype "passive"))
      (node (ref "Relay1") (pin "2") (pinfunction "LFB_2") (pintype "input"))
    )
    (net (code "34") (name "Net-(T1-B)") (class "Default")
      (node (ref "R13") (pin "2") (pinfunction "2_2") (pintype "passive"))
      (node (ref "T1") (pin "1") (pinfunction "B_1") (pintype "passive"))
    )
    (net (code "35") (name "Net-(T1-C)") (class "Default")
      (node (ref "R14") (pin "1") (pinfunction "1_1") (pintype "passive"))
      (node (ref "T1") (pin "3") (pinfunction "C_3") (pintype "passive"))
    )
    (net (code "36") (name "Net-(T2-B)") (class "Default")
      (node (ref "R18") (pin "2") (pinfunction "2_2") (pintype "passive"))
      (node (ref "T2") (pin "1") (pinfunction "B_1") (pintype "passive"))
    )
    (net (code "37") (name "Net-(T2-C)") (class "Default")
      (node (ref "R19") (pin "1") (pinfunction "1_1") (pintype "passive"))
      (node (ref "T2") (pin "3") (pinfunction "C_3") (pintype "passive"))
    )
    (net (code "38") (name "Net-(T3-B)") (class "Default")
      (node (ref "R21") (pin "2") (pinfunction "2_2") (pintype "passive"))
      (node (ref "T3") (pin "1") (pinfunction "B_1") (pintype "passive"))
    )
    (net (code "39") (name "Net-(T3-C)") (class "Default")
      (node (ref "R22") (pin "1") (pinfunction "1_1") (pintype "passive"))
      (node (ref "T3") (pin "3") (pinfunction "C_3") (pintype "passive"))
    )
    (net (code "40") (name "Net-(T3-E)") (class "Default")
      (node (ref "C2") (pin "2") (pinfunction "2_2") (pintype "passive"))
      (node (ref "R23") (pin "2") (pinfunction "2_2") (pintype "passive"))
      (node (ref "T3") (pin "2") (pinfunction "E_2") (pintype "passive"))
      (node (ref "U6") (pin "5") (pinfunction "OUT_B_5") (pintype "open_collector"))
    )
    (net (code "41") (name "Net-(T4-E)") (class "Default")
      (node (ref "R32") (pin "2") (pinfunction "2_2") (pintype "passive"))
      (node (ref "T4") (pin "2") (pinfunction "E_2") (pintype "passive"))
    )
    (net (code "42") (name "Net-(T5-E)") (class "Default")
      (node (ref "R33") (pin "1") (pinfunction "1_1") (pintype "passive"))
      (node (ref "T5") (pin "2") (pinfunction "E_2") (pintype "passive"))
    )
    (net (code "43") (name "Net-(T6-E)") (class "Default")
      (node (ref "R34") (pin "2") (pinfunction "2_2") (pintype "passive"))
      (node (ref "T6") (pin "2") (pinfunction "E_2") (pintype "passive"))
    )
    (net (code "44") (name "Net-(T7-E)") (class "Default")
      (node (ref "R35") (pin "1") (pinfunction "1_1") (pintype "passive"))
      (node (ref "T7") (pin "2") (pinfunction "E_2") (pintype "passive"))
    )
    (net (code "45") (name "Net-(T8-E)") (class "Default")
      (node (ref "R36") (pin "1") (pinfunction "1_1") (pintype "passive"))
      (node (ref "T8") (pin "2") (pinfunction "E_2") (pintype "passive"))
    )
    (net (code "46") (name "Net-(T9-E)") (class "Default")
      (node (ref "R37") (pin "2") (pinfunction "2_2") (pintype "passive"))
      (node (ref "T9") (pin "2") (pinfunction "E_2") (pintype "passive"))
    )
    (net (code "47") (name "Net-(TPS>25%-A)") (class "Default")
      (node (ref "R33") (pin "2") (pinfunction "2_2") (pintype "passive"))
      (node (ref "TPS>25%") (pin "2") (pinfunction "A_2") (pintype "passive"))
    )
    (net (code "48") (name "Net-(TPSShrtGND-A)") (class "Default")
      (node (ref "R32") (pin "1") (pinfunction "1_1") (pintype "passive"))
      (node (ref "TPSShrtGND") (pin "2") (pinfunction "A_2") (pintype "passive"))
    )
    (net (code "49") (name "Net-(Trimmpoti 2-WIPER)") (class "Default")
      (node (ref "R10") (pin "2") (pinfunction "2_2") (pintype "passive"))
      (node (ref "Trimmpoti 2") (pin "2") (pinfunction "WIPER_2") (pintype "passive"))
      (node (ref "U4") (pin "4") (pinfunction "-IN_B_4") (pintype "input"))
    )
    (net (code "50") (name "Net-(Trimmpoti-WIPER)") (class "Default")
      (node (ref "R3") (pin "2") (pinfunction "2_2") (pintype "passive"))
      (node (ref "Trimmpoti") (pin "2") (pinfunction "WIPER_2") (pintype "passive"))
      (node (ref "U1") (pin "4") (pinfunction "-IN_B_4") (pintype "input"))
    )
    (net (code "51") (name "Net-(U1A-+IN_A)") (class "Default")
      (node (ref "R1") (pin "1") (pinfunction "1_1") (pintype "passive"))
      (node (ref "R2") (pin "2") (pinfunction "2_2") (pintype "passive"))
      (node (ref "R6") (pin "1") (pinfunction "1_1") (pintype "passive"))
      (node (ref "U1") (pin "1") (pinfunction "+IN_A_1") (pintype "input"))
    )
    (net (code "52") (name "Net-(U1B-+IN_B)") (class "Default")
      (node (ref "R4") (pin "2") (pinfunction "2_2") (pintype "passive"))
      (node (ref "R5") (pin "1") (pinfunction "1_1") (pintype "passive"))
      (node (ref "U1") (pin "3") (pinfunction "+IN_B_3") (pintype "input"))
    )
    (net (code "53") (name "Net-(U4A-+IN_A)") (class "Default")
      (node (ref "R7") (pin "1") (pinfunction "1_1") (pintype "passive"))
      (node (ref "R8") (pin "2") (pinfunction "2_2") (pintype "passive"))
      (node (ref "R9") (pin "1") (pinfunction "1_1") (pintype "passive"))
      (node (ref "U4") (pin "1") (pinfunction "+IN_A_1") (pintype "input"))
    )
    (net (code "54") (name "Net-(U4B-+IN_B)") (class "Default")
      (node (ref "R11") (pin "2") (pinfunction "2_2") (pintype "passive"))
      (node (ref "R12") (pin "1") (pinfunction "1_1") (pintype "passive"))
      (node (ref "U4") (pin "3") (pinfunction "+IN_B_3") (pintype "input"))
    )
    (net (code "55") (name "Net-(U8A-+IN_A)") (class "Default")
      (node (ref "R26") (pin "2") (pinfunction "2_2") (pintype "passive"))
      (node (ref "R27") (pin "1") (pinfunction "1_1") (pintype "passive"))
      (node (ref "U8") (pin "1") (pinfunction "+IN_A_1") (pintype "input"))
    )
    (net (code "56") (name "Net-(U8A--IN_A)") (class "Default")
      (node (ref "R24") (pin "1") (pinfunction "1_1") (pintype "passive"))
      (node (ref "R25") (pin "2") (pinfunction "2_2") (pintype "passive"))
      (node (ref "U8") (pin "8") (pinfunction "-IN_A_8") (pintype "input"))
    )
    (net (code "57") (name "Net-(U8B-+IN_B)") (class "Default")
      (node (ref "R30") (pin "2") (pinfunction "2_2") (pintype "passive"))
      (node (ref "R31") (pin "1") (pinfunction "1_1") (pintype "passive"))
      (node (ref "U8") (pin "3") (pinfunction "+IN_B_3") (pintype "input"))
    )
    (net (code "58") (name "Net-(U8B--IN_B)") (class "Default")
      (node (ref "R28") (pin "1") (pinfunction "1_1") (pintype "passive"))
      (node (ref "R29") (pin "2") (pinfunction "2_2") (pintype "passive"))
      (node (ref "U8") (pin "4") (pinfunction "-IN_B_4") (pintype "input"))
    )
    (net (code "59") (name "unconnected-(OP1-NC-Pad1)") (class "Default")
      (node (ref "OP1") (pin "1") (pinfunction "NC_1") (pintype "input"))
    )
    (net (code "60") (name "unconnected-(OP1-NC-Pad5)") (class "Default")
      (node (ref "OP1") (pin "5") (pinfunction "NC_5") (pintype "input"))
    )
    (net (code "61") (name "unconnected-(OP1-NC-Pad8)") (class "Default")
      (node (ref "OP1") (pin "8") (pinfunction "NC_8") (pintype "input"))
    )
    (net (code "62") (name "unconnected-(OP2-NC-Pad1)") (class "Default")
      (node (ref "OP2") (pin "1") (pinfunction "NC_1") (pintype "input"))
    )
    (net (code "63") (name "unconnected-(OP2-NC-Pad5)") (class "Default")
      (node (ref "OP2") (pin "5") (pinfunction "NC_5") (pintype "input"))
    )
    (net (code "64") (name "unconnected-(OP2-NC-Pad8)") (class "Default")
      (node (ref "OP2") (pin "8") (pinfunction "NC_8") (pintype "input"))
    )
    (net (code "65") (name "unconnected-(Trimmpoti 2-CW-Pad3)") (class "Default")
      (node (ref "Trimmpoti 2") (pin "3") (pinfunction "CW_3") (pintype "passive"))
    )
    (net (code "66") (name "unconnected-(Trimmpoti-CW-Pad3)") (class "Default")
      (node (ref "Trimmpoti") (pin "3") (pinfunction "CW_3") (pintype "passive"))
    )
  )
)
